# SoundChip.net
KiCad netlist of a schematic drawn in Altium Designer
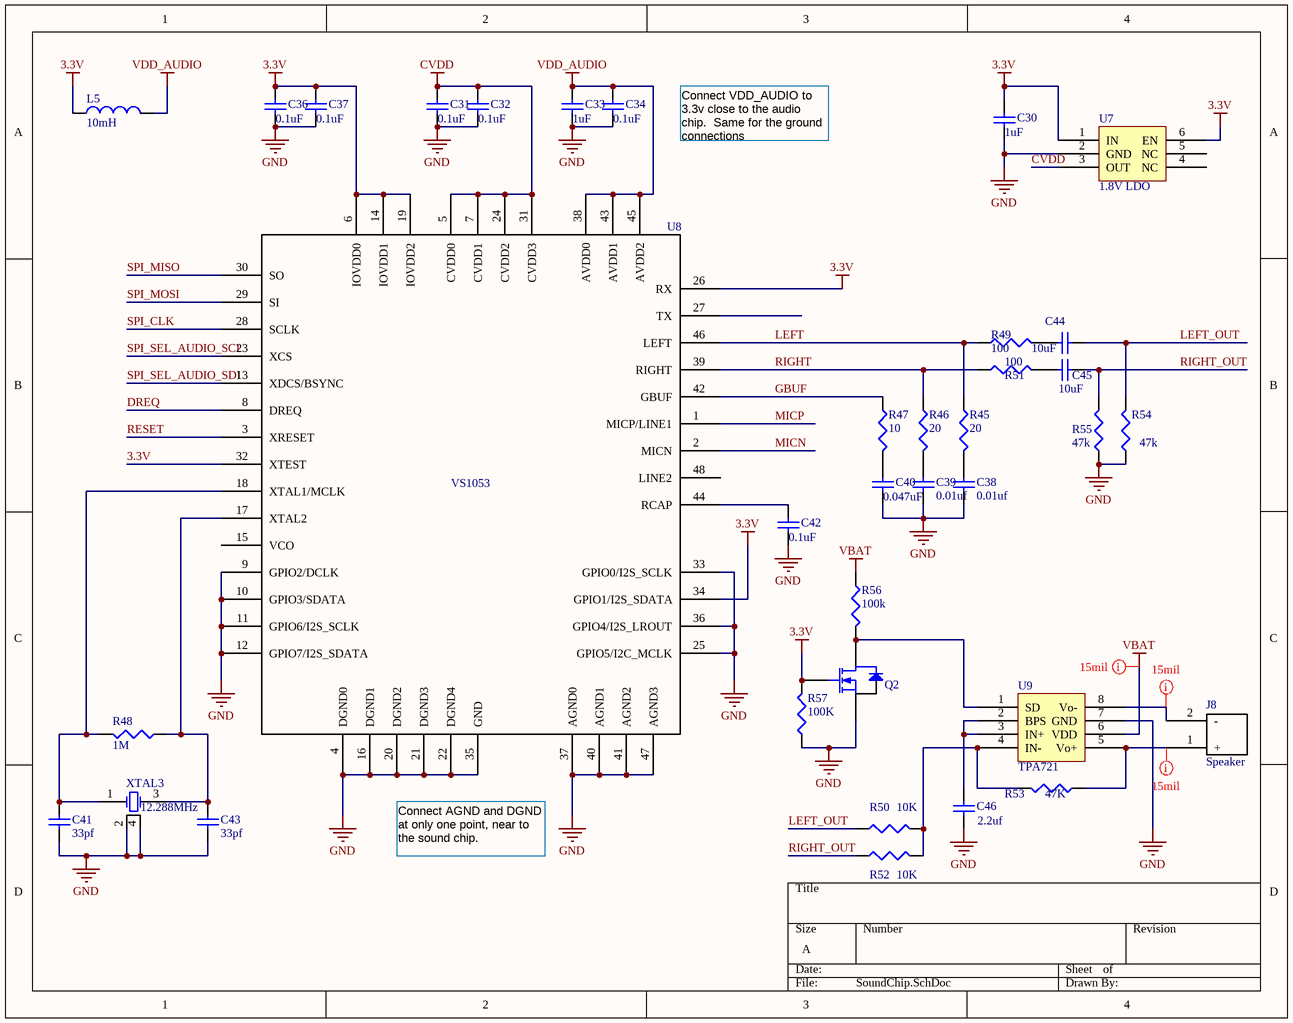
[diagram p0: SoundChip.SchDoc]

(export (version "E")
  (design (tool "Eeschema 10.0.6"))
  (components
    (comp (ref "C30")
      (value "1uF")
      (footprint "CAPC1608L")
      (description "Capacitor (Semiconductor SIM Model)")
      (fields (field (name "Comment") "Cap Semi") (field (name "PUBLISHER") "Altium Limited"))
      (libsource (lib "Miscellaneous Devices") (part "Cap Semi"))
    )
    (comp (ref "C31")
      (value "0.1uF")
      (footprint "CAPC1005L")
      (description "Capacitor (Semiconductor SIM Model)")
      (fields (field (name "Comment") "Cap Semi") (field (name "PUBLISHER") "Altium Limited"))
      (libsource (lib "Miscellaneous Devices") (part "Cap Semi"))
    )
    (comp (ref "C32")
      (value "0.1uF")
      (footprint "CAPC1005L")
      (description "Capacitor (Semiconductor SIM Model)")
      (fields (field (name "Comment") "Cap Semi") (field (name "PUBLISHER") "Altium Limited"))
      (libsource (lib "Miscellaneous Devices") (part "Cap Semi"))
    )
    (comp (ref "C33")
      (value "1uF")
      (footprint "CAPC1608L")
      (description "Capacitor (Semiconductor SIM Model)")
      (fields (field (name "Comment") "Cap Semi") (field (name "PUBLISHER") "Altium Limited"))
      (libsource (lib "Miscellaneous Devices") (part "Cap Semi"))
    )
    (comp (ref "C34")
      (value "0.1uF")
      (footprint "CAPC1005L")
      (description "Capacitor (Semiconductor SIM Model)")
      (fields (field (name "Comment") "Cap Semi") (field (name "PUBLISHER") "Altium Limited"))
      (libsource (lib "Miscellaneous Devices") (part "Cap Semi"))
    )
    (comp (ref "C36")
      (value "0.1uF")
      (footprint "CAPC1005L")
      (description "Capacitor (Semiconductor SIM Model)")
      (fields (field (name "Comment") "Cap Semi") (field (name "PUBLISHER") "Altium Limited"))
      (libsource (lib "Miscellaneous Devices") (part "Cap Semi"))
    )
    (comp (ref "C37")
      (value "0.1uF")
      (footprint "CAPC1005L")
      (description "Capacitor (Semiconductor SIM Model)")
      (fields (field (name "Comment") "Cap Semi") (field (name "PUBLISHER") "Altium Limited"))
      (libsource (lib "Miscellaneous Devices") (part "Cap Semi"))
    )
    (comp (ref "C38")
      (value "0.01uf")
      (footprint "CAPC1005L")
      (description "Capacitor (Semiconductor SIM Model)")
      (fields (field (name "Comment") "Cap Semi") (field (name "PUBLISHER") "Altium Limited"))
      (libsource (lib "Miscellaneous Devices") (part "Cap Semi"))
    )
    (comp (ref "C39")
      (value "0.01uf")
      (footprint "CAPC1005L")
      (description "Capacitor (Semiconductor SIM Model)")
      (fields (field (name "Comment") "Cap Semi") (field (name "PUBLISHER") "Altium Limited"))
      (libsource (lib "Miscellaneous Devices") (part "Cap Semi"))
    )
    (comp (ref "C40")
      (value "0.047uF")
      (footprint "CAPC1005L")
      (description "Capacitor (Semiconductor SIM Model)")
      (fields (field (name "Comment") "Cap Semi") (field (name "PUBLISHER") "Altium Limited"))
      (libsource (lib "Miscellaneous Devices") (part "Cap Semi"))
    )
    (comp (ref "C41")
      (value "33pf")
      (footprint "CAPC1005L")
      (description "Capacitor (Semiconductor SIM Model)")
      (fields (field (name "Comment") "Cap Semi") (field (name "PUBLISHER") "Altium Limited"))
      (libsource (lib "Miscellaneous Devices") (part "Cap Semi"))
    )
    (comp (ref "C42")
      (value "0.1uF")
      (footprint "CAPC1005L")
      (description "Capacitor (Semiconductor SIM Model)")
      (fields (field (name "Comment") "Cap Semi") (field (name "PUBLISHER") "Altium Limited"))
      (libsource (lib "Miscellaneous Devices") (part "Cap Semi"))
    )
    (comp (ref "C43")
      (value "33pf")
      (footprint "CAPC1005L")
      (description "Capacitor (Semiconductor SIM Model)")
      (fields (field (name "Comment") "Cap Semi") (field (name "PUBLISHER") "Altium Limited"))
      (libsource (lib "Miscellaneous Devices") (part "Cap Semi"))
    )
    (comp (ref "C44")
      (value "10uF")
      (footprint "CAPC3216L")
      (description "Capacitor (Semiconductor SIM Model)")
      (fields (field (name "Comment") "Cap Semi") (field (name "PUBLISHER") "Altium Limited"))
      (libsource (lib "Miscellaneous Devices") (part "Cap Semi"))
    )
    (comp (ref "C45")
      (value "10uF")
      (footprint "CAPC3216L")
      (description "Capacitor (Semiconductor SIM Model)")
      (fields (field (name "Comment") "Cap Semi") (field (name "PUBLISHER") "Altium Limited"))
      (libsource (lib "Miscellaneous Devices") (part "Cap Semi"))
    )
    (comp (ref "C46")
      (value "2.2uf")
      (footprint "CAPC1608L")
      (description "Capacitor (Semiconductor SIM Model)")
      (fields (field (name "Comment") "Cap Semi") (field (name "PUBLISHER") "Altium Limited"))
      (libsource (lib "Miscellaneous Devices") (part "Cap Semi"))
    )
    (comp (ref "J8")
      (value "Speaker")
      (footprint "BatteryConnJST")
      (libsource (lib "mrone") (part "BatteryConnJST"))
    )
    (comp (ref "L5")
      (value "10mH")
      (footprint "INDC2012L")
      (description "Inductor")
      (fields (field (name "PUBLISHER") "Altium Limited"))
      (libsource (lib "Miscellaneous Devices") (part "Inductor"))
    )
    (comp (ref "Q2") (value "Mosfet") (footprint "SOT-23") (libsource (lib "mrone") (part "Mosfet")))
    (comp (ref "R45")
      (value "20")
      (footprint "RESC1608L")
      (description "Resistor")
      (fields (field (name "Comment") "Res3") (field (name "PUBLISHER") "Altium Limited"))
      (libsource (lib "Miscellaneous Devices") (part "Res3"))
    )
    (comp (ref "R46")
      (value "20")
      (footprint "RESC1608L")
      (description "Resistor")
      (fields (field (name "Comment") "Res3") (field (name "PUBLISHER") "Altium Limited"))
      (libsource (lib "Miscellaneous Devices") (part "Res3"))
    )
    (comp (ref "R47")
      (value "10")
      (footprint "RESC1608L")
      (description "Resistor")
      (fields (field (name "Comment") "Res3") (field (name "PUBLISHER") "Altium Limited"))
      (libsource (lib "Miscellaneous Devices") (part "Res3"))
    )
    (comp (ref "R48")
      (value "1M")
      (footprint "RESC1608L")
      (description "Resistor")
      (fields (field (name "Comment") "Res3") (field (name "PUBLISHER") "Altium Limited"))
      (libsource (lib "Miscellaneous Devices") (part "Res3"))
    )
    (comp (ref "R49")
      (value "100")
      (footprint "RESC1608L")
      (description "Resistor")
      (fields (field (name "Comment") "Res3") (field (name "PUBLISHER") "Altium Limited"))
      (libsource (lib "Miscellaneous Devices") (part "Res3"))
    )
    (comp (ref "R50")
      (value "10K")
      (footprint "RESC1608L")
      (description "Resistor")
      (fields (field (name "Comment") "Res3") (field (name "PUBLISHER") "Altium Limited"))
      (libsource (lib "Miscellaneous Devices") (part "Res3"))
    )
    (comp (ref "R51")
      (value "100")
      (footprint "RESC1608L")
      (description "Resistor")
      (fields (field (name "Comment") "Res3") (field (name "PUBLISHER") "Altium Limited"))
      (libsource (lib "Miscellaneous Devices") (part "Res3"))
    )
    (comp (ref "R52")
      (value "10K")
      (footprint "RESC1608L")
      (description "Resistor")
      (fields (field (name "Comment") "Res3") (field (name "PUBLISHER") "Altium Limited"))
      (libsource (lib "Miscellaneous Devices") (part "Res3"))
    )
    (comp (ref "R53")
      (value "47K")
      (footprint "RESC1608L")
      (description "Resistor")
      (fields (field (name "Comment") "Res3") (field (name "PUBLISHER") "Altium Limited"))
      (libsource (lib "Miscellaneous Devices") (part "Res3"))
    )
    (comp (ref "R54")
      (value "47k")
      (footprint "RESC1608L")
      (description "Resistor")
      (fields (field (name "Comment") "Res3") (field (name "PUBLISHER") "Altium Limited"))
      (libsource (lib "Miscellaneous Devices") (part "Res3"))
    )
    (comp (ref "R55")
      (value "47k")
      (footprint "RESC1608L")
      (description "Resistor")
      (fields (field (name "Comment") "Res3") (field (name "PUBLISHER") "Altium Limited"))
      (libsource (lib "Miscellaneous Devices") (part "Res3"))
    )
    (comp (ref "R56")
      (value "100k")
      (footprint "RESC1608L")
      (description "Resistor")
      (fields (field (name "Comment") "Res3") (field (name "PUBLISHER") "Altium Limited"))
      (libsource (lib "Miscellaneous Devices") (part "Res3"))
    )
    (comp (ref "R57")
      (value "100K")
      (footprint "RESC1608L")
      (description "Resistor")
      (fields (field (name "Comment") "Res3") (field (name "PUBLISHER") "Altium Limited"))
      (libsource (lib "Miscellaneous Devices") (part "Res3"))
    )
    (comp (ref "U7") (value "1.8V LDO") (footprint "WFDFN-6") (libsource (lib "mrone") (part "1.8V_LDO")))
    (comp (ref "U8") (value "VS1053") (footprint "LQFP-48") (libsource (lib "mrone") (part "VS1053")))
    (comp (ref "U9")
      (value "TPA721")
      (footprint "SOIC8-AMP")
      (libsource (lib "mrone") (part "AudioAmpTPA721"))
    )
    (comp (ref "XTAL3") (value "12.288MHz") (footprint "CRYSTAL") (libsource (lib "mrone") (part "Crystal")))
  )
  (nets
    (net (code "1") (name "/DREQ") (class "Default")
      (node (ref "U8") (pin "8") (pinfunction "DREQ_8") (pintype "passive"))
    )
    (net (code "2") (name "/GBUF") (class "Default")
      (node (ref "R47") (pin "1") (pinfunction "1_1") (pintype "passive"))
      (node (ref "U8") (pin "42") (pinfunction "GBUF_42") (pintype "passive"))
    )
    (net (code "3") (name "/LEFT") (class "Default")
      (node (ref "R45") (pin "1") (pinfunction "1_1") (pintype "passive"))
      (node (ref "R49") (pin "1") (pinfunction "1_1") (pintype "passive"))
      (node (ref "U8") (pin "46") (pinfunction "LEFT_46") (pintype "passive"))
    )
    (net (code "4") (name "/LEFT_OUT") (class "Default")
      (node (ref "C44") (pin "1") (pinfunction "1_1") (pintype "passive"))
      (node (ref "R50") (pin "1") (pinfunction "1_1") (pintype "passive"))
      (node (ref "R54") (pin "2") (pinfunction "2_2") (pintype "passive"))
    )
    (net (code "5") (name "/MICN") (class "Default")
      (node (ref "U8") (pin "2") (pinfunction "MICN_2") (pintype "passive"))
    )
    (net (code "6") (name "/MICP") (class "Default")
      (node (ref "U8") (pin "1") (pinfunction "MICP/LINE1_1") (pintype "passive"))
    )
    (net (code "7") (name "/RESET") (class "Default")
      (node (ref "U8") (pin "3") (pinfunction "XRESET_3") (pintype "passive"))
    )
    (net (code "8") (name "/RIGHT") (class "Default")
      (node (ref "R46") (pin "1") (pinfunction "1_1") (pintype "passive"))
      (node (ref "R51") (pin "1") (pinfunction "1_1") (pintype "passive"))
      (node (ref "U8") (pin "39") (pinfunction "RIGHT_39") (pintype "passive"))
    )
    (net (code "9") (name "/RIGHT_OUT") (class "Default")
      (node (ref "C45") (pin "1") (pinfunction "1_1") (pintype "passive"))
      (node (ref "R52") (pin "1") (pinfunction "1_1") (pintype "passive"))
      (node (ref "R55") (pin "2") (pinfunction "2_2") (pintype "passive"))
    )
    (net (code "10") (name "/SPI_CLK") (class "Default")
      (node (ref "U8") (pin "28") (pinfunction "SCLK_28") (pintype "passive"))
    )
    (net (code "11") (name "/SPI_MISO") (class "Default")
      (node (ref "U8") (pin "30") (pinfunction "SO_30") (pintype "passive"))
    )
    (net (code "12") (name "/SPI_MOSI") (class "Default")
      (node (ref "U8") (pin "29") (pinfunction "SI_29") (pintype "passive"))
    )
    (net (code "13") (name "/SPI_SEL_AUDIO_SCI") (class "Default")
      (node (ref "U8") (pin "23") (pinfunction "XCS_23") (pintype "passive"))
    )
    (net (code "14") (name "/SPI_SEL_AUDIO_SDI") (class "Default")
      (node (ref "U8") (pin "13") (pinfunction "XDCS/BSYNC_13") (pintype "passive"))
    )
    (net (code "15") (name "3.3V") (class "Default")
      (node (ref "C30") (pin "1") (pinfunction "1_1") (pintype "passive"))
      (node (ref "C36") (pin "2") (pinfunction "2_2") (pintype "passive"))
      (node (ref "C37") (pin "2") (pinfunction "2_2") (pintype "passive"))
      (node (ref "L5") (pin "2") (pinfunction "2_2") (pintype "passive"))
      (node (ref "Q2") (pin "1") (pinfunction "G_1") (pintype "passive"))
      (node (ref "R57") (pin "2") (pinfunction "2_2") (pintype "passive"))
      (node (ref "U7") (pin "1") (pinfunction "IN_1") (pintype "passive"))
      (node (ref "U7") (pin "6") (pinfunction "EN_6") (pintype "passive"))
      (node (ref "U8") (pin "14") (pinfunction "IOVDD1_14") (pintype "passive"))
      (node (ref "U8") (pin "19") (pinfunction "IOVDD2_19") (pintype "passive"))
      (node (ref "U8") (pin "26") (pinfunction "RX_26") (pintype "passive"))
      (node (ref "U8") (pin "32") (pinfunction "XTEST_32") (pintype "passive"))
      (node (ref "U8") (pin "34") (pinfunction "GPIO1/I2S_SDATA_34") (pintype "passive"))
      (node (ref "U8") (pin "6") (pinfunction "IOVDD0_6") (pintype "passive"))
    )
    (net (code "16") (name "CVDD") (class "Default")
      (node (ref "C31") (pin "2") (pinfunction "2_2") (pintype "passive"))
      (node (ref "C32") (pin "2") (pinfunction "2_2") (pintype "passive"))
      (node (ref "U7") (pin "3") (pinfunction "OUT_3") (pintype "passive"))
      (node (ref "U8") (pin "24") (pinfunction "CVDD2_24") (pintype "passive"))
      (node (ref "U8") (pin "31") (pinfunction "CVDD3_31") (pintype "passive"))
      (node (ref "U8") (pin "5") (pinfunction "CVDD0_5") (pintype "passive"))
      (node (ref "U8") (pin "7") (pinfunction "CVDD1_7") (pintype "passive"))
    )
    (net (code "17") (name "GND") (class "Default")
      (node (ref "C30") (pin "2") (pinfunction "2_2") (pintype "passive"))
      (node (ref "C31") (pin "1") (pinfunction "1_1") (pintype "passive"))
      (node (ref "C32") (pin "1") (pinfunction "1_1") (pintype "passive"))
      (node (ref "C33") (pin "2") (pinfunction "2_2") (pintype "passive"))
      (node (ref "C34") (pin "1") (pinfunction "1_1") (pintype "passive"))
      (node (ref "C36") (pin "1") (pinfunction "1_1") (pintype "passive"))
      (node (ref "C37") (pin "1") (pinfunction "1_1") (pintype "passive"))
      (node (ref "C38") (pin "2") (pinfunction "2_2") (pintype "passive"))
      (node (ref "C39") (pin "2") (pinfunction "2_2") (pintype "passive"))
      (node (ref "C40") (pin "2") (pinfunction "2_2") (pintype "passive"))
      (node (ref "C41") (pin "2") (pinfunction "2_2") (pintype "passive"))
      (node (ref "C42") (pin "1") (pinfunction "1_1") (pintype "passive"))
      (node (ref "C43") (pin "2") (pinfunction "2_2") (pintype "passive"))
      (node (ref "C46") (pin "1") (pinfunction "1_1") (pintype "passive"))
      (node (ref "Q2") (pin "2") (pinfunction "S_2") (pintype "passive"))
      (node (ref "R54") (pin "1") (pinfunction "1_1") (pintype "passive"))
      (node (ref "R55") (pin "1") (pinfunction "1_1") (pintype "passive"))
      (node (ref "R57") (pin "1") (pinfunction "1_1") (pintype "passive"))
      (node (ref "U7") (pin "2") (pinfunction "GND_2") (pintype "passive"))
      (node (ref "U8") (pin "10") (pinfunction "GPIO3/SDATA_10") (pintype "passive"))
      (node (ref "U8") (pin "11") (pinfunction "GPIO6/I2S_SCLK_11") (pintype "passive"))
      (node (ref "U8") (pin "12") (pinfunction "GPIO7/I2S_SDATA_12") (pintype "passive"))
      (node (ref "U8") (pin "16") (pinfunction "DGND1_16") (pintype "passive"))
      (node (ref "U8") (pin "20") (pinfunction "DGND2_20") (pintype "passive"))
      (node (ref "U8") (pin "21") (pinfunction "DGND3_21") (pintype "passive"))
      (node (ref "U8") (pin "22") (pinfunction "DGND4_22") (pintype "passive"))
      (node (ref "U8") (pin "25") (pinfunction "GPIO5/I2C_MCLK_25") (pintype "passive"))
      (node (ref "U8") (pin "33") (pinfunction "GPIO0/I2S_SCLK_33") (pintype "passive"))
      (node (ref "U8") (pin "35") (pinfunction "GND_35") (pintype "passive"))
      (node (ref "U8") (pin "36") (pinfunction "GPIO4/I2S_LROUT_36") (pintype "passive"))
      (node (ref "U8") (pin "37") (pinfunction "AGND0_37") (pintype "passive"))
      (node (ref "U8") (pin "4") (pinfunction "DGND0_4") (pintype "passive"))
      (node (ref "U8") (pin "40") (pinfunction "AGND1_40") (pintype "passive"))
      (node (ref "U8") (pin "41") (pinfunction "AGND2_41") (pintype "passive"))
      (node (ref "U8") (pin "47") (pinfunction "AGND3_47") (pintype "passive"))
      (node (ref "U8") (pin "9") (pinfunction "GPIO2/DCLK_9") (pintype "passive"))
      (node (ref "U9") (pin "7") (pinfunction "GND_7") (pintype "passive"))
      (node (ref "XTAL3") (pin "2") (pinfunction "GND_2") (pintype "passive"))
      (node (ref "XTAL3") (pin "4") (pinfunction "GND_4") (pintype "passive"))
    )
    (net (code "18") (name "Net-(C38-Pad1)") (class "Default")
      (node (ref "C38") (pin "1") (pinfunction "1_1") (pintype "passive"))
      (node (ref "R45") (pin "2") (pinfunction "2_2") (pintype "passive"))
    )
    (net (code "19") (name "Net-(C39-Pad1)") (class "Default")
      (node (ref "C39") (pin "1") (pinfunction "1_1") (pintype "passive"))
      (node (ref "R46") (pin "2") (pinfunction "2_2") (pintype "passive"))
    )
    (net (code "20") (name "Net-(C40-Pad1)") (class "Default")
      (node (ref "C40") (pin "1") (pinfunction "1_1") (pintype "passive"))
      (node (ref "R47") (pin "2") (pinfunction "2_2") (pintype "passive"))
    )
    (net (code "21") (name "Net-(C44-Pad2)") (class "Default")
      (node (ref "C44") (pin "2") (pinfunction "2_2") (pintype "passive"))
      (node (ref "R49") (pin "2") (pinfunction "2_2") (pintype "passive"))
    )
    (net (code "22") (name "Net-(C45-Pad2)") (class "Default")
      (node (ref "C45") (pin "2") (pinfunction "2_2") (pintype "passive"))
      (node (ref "R51") (pin "2") (pinfunction "2_2") (pintype "passive"))
    )
    (net (code "23") (name "Net-(J8-+)") (class "Default")
      (node (ref "J8") (pin "1") (pinfunction "+_1") (pintype "passive"))
      (node (ref "R53") (pin "1") (pinfunction "1_1") (pintype "passive"))
      (node (ref "U9") (pin "5") (pinfunction "Vo+_5") (pintype "passive"))
    )
    (net (code "24") (name "Net-(J8--)") (class "Default")
      (node (ref "J8") (pin "2") (pinfunction "-_2") (pintype "passive"))
      (node (ref "U9") (pin "8") (pinfunction "Vo-_8") (pintype "passive"))
    )
    (net (code "25") (name "Net-(Q2-D)") (class "Default")
      (node (ref "Q2") (pin "3") (pinfunction "D_3") (pintype "passive"))
      (node (ref "R56") (pin "1") (pinfunction "1_1") (pintype "passive"))
      (node (ref "U9") (pin "1") (pinfunction "SD_1") (pintype "passive"))
    )
    (net (code "26") (name "Net-(U8-RCAP)") (class "Default")
      (node (ref "C42") (pin "2") (pinfunction "2_2") (pintype "passive"))
      (node (ref "U8") (pin "44") (pinfunction "RCAP_44") (pintype "passive"))
    )
    (net (code "27") (name "Net-(U8-XTAL1{slash}MCLK)") (class "Default")
      (node (ref "C41") (pin "1") (pinfunction "1_1") (pintype "passive"))
      (node (ref "R48") (pin "2") (pinfunction "2_2") (pintype "passive"))
      (node (ref "U8") (pin "18") (pinfunction "XTAL1/MCLK_18") (pintype "passive"))
      (node (ref "XTAL3") (pin "1") (pinfunction "OSC1_1") (pintype "passive"))
    )
    (net (code "28") (name "Net-(U8-XTAL2)") (class "Default")
      (node (ref "C43") (pin "1") (pinfunction "1_1") (pintype "passive"))
      (node (ref "R48") (pin "1") (pinfunction "1_1") (pintype "passive"))
      (node (ref "U8") (pin "17") (pinfunction "XTAL2_17") (pintype "passive"))
      (node (ref "XTAL3") (pin "3") (pinfunction "OSC2_3") (pintype "passive"))
    )
    (net (code "29") (name "Net-(U9-BPS)") (class "Default")
      (node (ref "C46") (pin "2") (pinfunction "2_2") (pintype "passive"))
      (node (ref "U9") (pin "2") (pinfunction "BPS_2") (pintype "passive"))
      (node (ref "U9") (pin "3") (pinfunction "IN+_3") (pintype "passive"))
    )
    (net (code "30") (name "Net-(U9-IN-)") (class "Default")
      (node (ref "R50") (pin "2") (pinfunction "2_2") (pintype "passive"))
      (node (ref "R52") (pin "2") (pinfunction "2_2") (pintype "passive"))
      (node (ref "R53") (pin "2") (pinfunction "2_2") (pintype "passive"))
      (node (ref "U9") (pin "4") (pinfunction "IN-_4") (pintype "passive"))
    )
    (net (code "31") (name "VBAT") (class "Default")
      (node (ref "R56") (pin "2") (pinfunction "2_2") (pintype "passive"))
      (node (ref "U9") (pin "6") (pinfunction "VDD_6") (pintype "passive"))
    )
    (net (code "32") (name "VDD_AUDIO") (class "Default")
      (node (ref "C33") (pin "1") (pinfunction "1_1") (pintype "passive"))
      (node (ref "C34") (pin "2") (pinfunction "2_2") (pintype "passive"))
      (node (ref "L5") (pin "1") (pinfunction "1_1") (pintype "passive"))
      (node (ref "U8") (pin "38") (pinfunction "AVDD0_38") (pintype "passive"))
      (node (ref "U8") (pin "43") (pinfunction "AVDD1_43") (pintype "passive"))
      (node (ref "U8") (pin "45") (pinfunction "AVDD2_45") (pintype "passive"))
    )
    (net (code "33") (name "unconnected-(U7-NC-Pad4)") (class "Default")
      (node (ref "U7") (pin "4") (pinfunction "NC_4") (pintype "passive"))
    )
    (net (code "34") (name "unconnected-(U7-NC-Pad5)") (class "Default")
      (node (ref "U7") (pin "5") (pinfunction "NC_5") (pintype "passive"))
    )
    (net (code "35") (name "unconnected-(U8-LINE2-Pad48)") (class "Default")
      (node (ref "U8") (pin "48") (pinfunction "LINE2_48") (pintype "passive"))
    )
    (net (code "36") (name "unconnected-(U8-TX-Pad27)") (class "Default")
      (node (ref "U8") (pin "27") (pinfunction "TX_27") (pintype "passive"))
    )
    (net (code "37") (name "unconnected-(U8-VCO-Pad15)") (class "Default")
      (node (ref "U8") (pin "15") (pinfunction "VCO_15") (pintype "passive"))
    )
  )
)
